# bulk_capacitance.net
KiCad netlist of a schematic drawn in Altium Designer
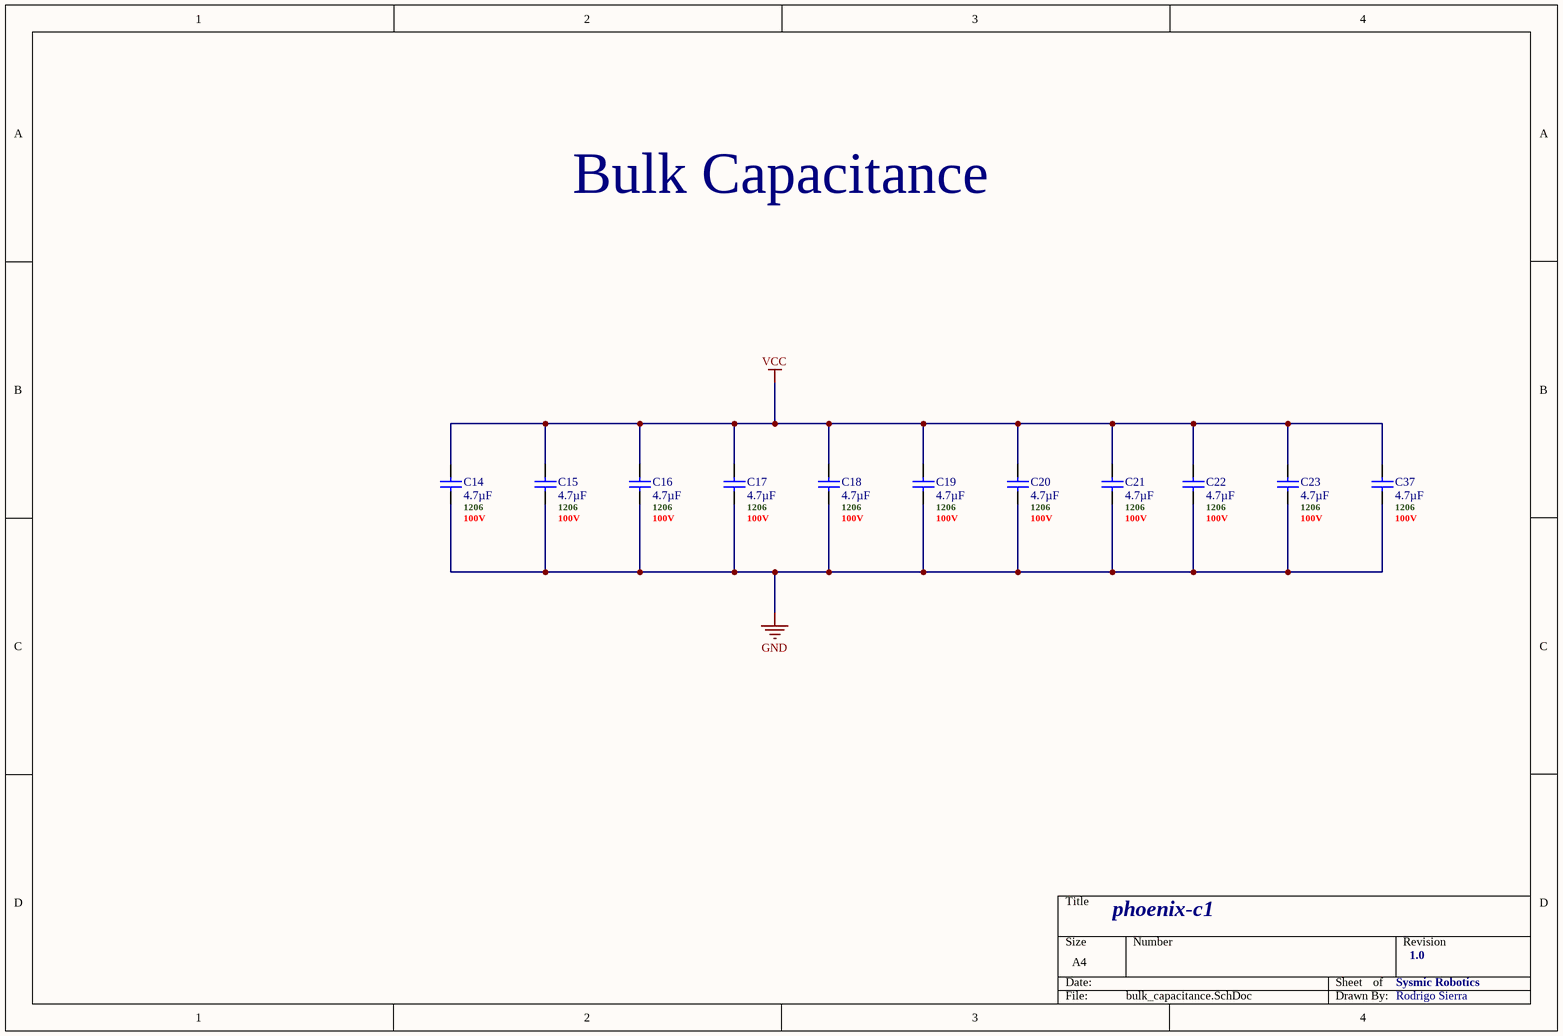
[diagram p0: bulk_capacitance.SchDoc]

(export (version "E")
  (design (tool "Eeschema 10.0.6"))
  (components
    (comp (ref "C14")
      (value "4.7µF")
      (footprint "C1206 - MURATA")
      (fields
        (field (name "MANUFACTURER") "Murata")
        (field (name "MANUFACTURER PART NUMBER") "GRJ31CC72A475KE01K")
        (field (name ".CASE/PACKAGE") "1206")
        (field (name ".VOLTAGE RATING (DC)") "100V")
      )
      (libsource (lib "CAP - GRJ31CC72A475KE01K") (part "GRJ31CC72A475KE01K"))
    )
    (comp (ref "C15")
      (value "4.7µF")
      (footprint "C1206 - MURATA")
      (fields
        (field (name "MANUFACTURER") "Murata")
        (field (name "MANUFACTURER PART NUMBER") "GRJ31CC72A475KE01K")
        (field (name ".CASE/PACKAGE") "1206")
        (field (name ".VOLTAGE RATING (DC)") "100V")
      )
      (libsource (lib "CAP - GRJ31CC72A475KE01K") (part "GRJ31CC72A475KE01K"))
    )
    (comp (ref "C16")
      (value "4.7µF")
      (footprint "C1206 - MURATA")
      (fields
        (field (name "MANUFACTURER") "Murata")
        (field (name "MANUFACTURER PART NUMBER") "GRJ31CC72A475KE01K")
        (field (name ".CASE/PACKAGE") "1206")
        (field (name ".VOLTAGE RATING (DC)") "100V")
      )
      (libsource (lib "CAP - GRJ31CC72A475KE01K") (part "GRJ31CC72A475KE01K"))
    )
    (comp (ref "C17")
      (value "4.7µF")
      (footprint "C1206 - MURATA")
      (fields
        (field (name "MANUFACTURER") "Murata")
        (field (name "MANUFACTURER PART NUMBER") "GRJ31CC72A475KE01K")
        (field (name ".CASE/PACKAGE") "1206")
        (field (name ".VOLTAGE RATING (DC)") "100V")
      )
      (libsource (lib "CAP - GRJ31CC72A475KE01K") (part "GRJ31CC72A475KE01K"))
    )
    (comp (ref "C18")
      (value "4.7µF")
      (footprint "C1206 - MURATA")
      (fields
        (field (name "MANUFACTURER") "Murata")
        (field (name "MANUFACTURER PART NUMBER") "GRJ31CC72A475KE01K")
        (field (name ".CASE/PACKAGE") "1206")
        (field (name ".VOLTAGE RATING (DC)") "100V")
      )
      (libsource (lib "CAP - GRJ31CC72A475KE01K") (part "GRJ31CC72A475KE01K"))
    )
    (comp (ref "C19")
      (value "4.7µF")
      (footprint "C1206 - MURATA")
      (fields
        (field (name "MANUFACTURER") "Murata")
        (field (name "MANUFACTURER PART NUMBER") "GRJ31CC72A475KE01K")
        (field (name ".CASE/PACKAGE") "1206")
        (field (name ".VOLTAGE RATING (DC)") "100V")
      )
      (libsource (lib "CAP - GRJ31CC72A475KE01K") (part "GRJ31CC72A475KE01K"))
    )
    (comp (ref "C20")
      (value "4.7µF")
      (footprint "C1206 - MURATA")
      (fields
        (field (name "MANUFACTURER") "Murata")
        (field (name "MANUFACTURER PART NUMBER") "GRJ31CC72A475KE01K")
        (field (name ".CASE/PACKAGE") "1206")
        (field (name ".VOLTAGE RATING (DC)") "100V")
      )
      (libsource (lib "CAP - GRJ31CC72A475KE01K") (part "GRJ31CC72A475KE01K"))
    )
    (comp (ref "C21")
      (value "4.7µF")
      (footprint "C1206 - MURATA")
      (fields
        (field (name "MANUFACTURER") "Murata")
        (field (name "MANUFACTURER PART NUMBER") "GRJ31CC72A475KE01K")
        (field (name ".CASE/PACKAGE") "1206")
        (field (name ".VOLTAGE RATING (DC)") "100V")
      )
      (libsource (lib "CAP - GRJ31CC72A475KE01K") (part "GRJ31CC72A475KE01K"))
    )
    (comp (ref "C22")
      (value "4.7µF")
      (footprint "C1206 - MURATA")
      (fields
        (field (name "MANUFACTURER") "Murata")
        (field (name "MANUFACTURER PART NUMBER") "GRJ31CC72A475KE01K")
        (field (name ".CASE/PACKAGE") "1206")
        (field (name ".VOLTAGE RATING (DC)") "100V")
      )
      (libsource (lib "CAP - GRJ31CC72A475KE01K") (part "GRJ31CC72A475KE01K"))
    )
    (comp (ref "C23")
      (value "4.7µF")
      (footprint "C1206 - MURATA")
      (fields
        (field (name "MANUFACTURER") "Murata")
        (field (name "MANUFACTURER PART NUMBER") "GRJ31CC72A475KE01K")
        (field (name ".CASE/PACKAGE") "1206")
        (field (name ".VOLTAGE RATING (DC)") "100V")
      )
      (libsource (lib "CAP - GRJ31CC72A475KE01K") (part "GRJ31CC72A475KE01K"))
    )
    (comp (ref "C37")
      (value "4.7µF")
      (footprint "C1206 - MURATA")
      (fields
        (field (name "MANUFACTURER") "Murata")
        (field (name "MANUFACTURER PART NUMBER") "GRJ31CC72A475KE01K")
        (field (name ".CASE/PACKAGE") "1206")
        (field (name ".VOLTAGE RATING (DC)") "100V")
      )
      (libsource (lib "CAP - GRJ31CC72A475KE01K") (part "GRJ31CC72A475KE01K"))
    )
  )
  (nets
    (net (code "1") (name "GND") (class "Default")
      (node (ref "C14") (pin "2") (pinfunction "2_2") (pintype "passive"))
      (node (ref "C15") (pin "2") (pinfunction "2_2") (pintype "passive"))
      (node (ref "C16") (pin "2") (pinfunction "2_2") (pintype "passive"))
      (node (ref "C17") (pin "2") (pinfunction "2_2") (pintype "passive"))
      (node (ref "C18") (pin "2") (pinfunction "2_2") (pintype "passive"))
      (node (ref "C19") (pin "2") (pinfunction "2_2") (pintype "passive"))
      (node (ref "C20") (pin "2") (pinfunction "2_2") (pintype "passive"))
      (node (ref "C21") (pin "2") (pinfunction "2_2") (pintype "passive"))
      (node (ref "C22") (pin "2") (pinfunction "2_2") (pintype "passive"))
      (node (ref "C23") (pin "2") (pinfunction "2_2") (pintype "passive"))
      (node (ref "C37") (pin "2") (pinfunction "2_2") (pintype "passive"))
    )
    (net (code "2") (name "VCC") (class "Default")
      (node (ref "C14") (pin "1") (pinfunction "1_1") (pintype "passive"))
      (node (ref "C15") (pin "1") (pinfunction "1_1") (pintype "passive"))
      (node (ref "C16") (pin "1") (pinfunction "1_1") (pintype "passive"))
      (node (ref "C17") (pin "1") (pinfunction "1_1") (pintype "passive"))
      (node (ref "C18") (pin "1") (pinfunction "1_1") (pintype "passive"))
      (node (ref "C19") (pin "1") (pinfunction "1_1") (pintype "passive"))
      (node (ref "C20") (pin "1") (pinfunction "1_1") (pintype "passive"))
      (node (ref "C21") (pin "1") (pinfunction "1_1") (pintype "passive"))
      (node (ref "C22") (pin "1") (pinfunction "1_1") (pintype "passive"))
      (node (ref "C23") (pin "1") (pinfunction "1_1") (pintype "passive"))
      (node (ref "C37") (pin "1") (pinfunction "1_1") (pintype "passive"))
    )
  )
)
